# Board_connectors.net
KiCad netlist of a schematic drawn in Altium Designer
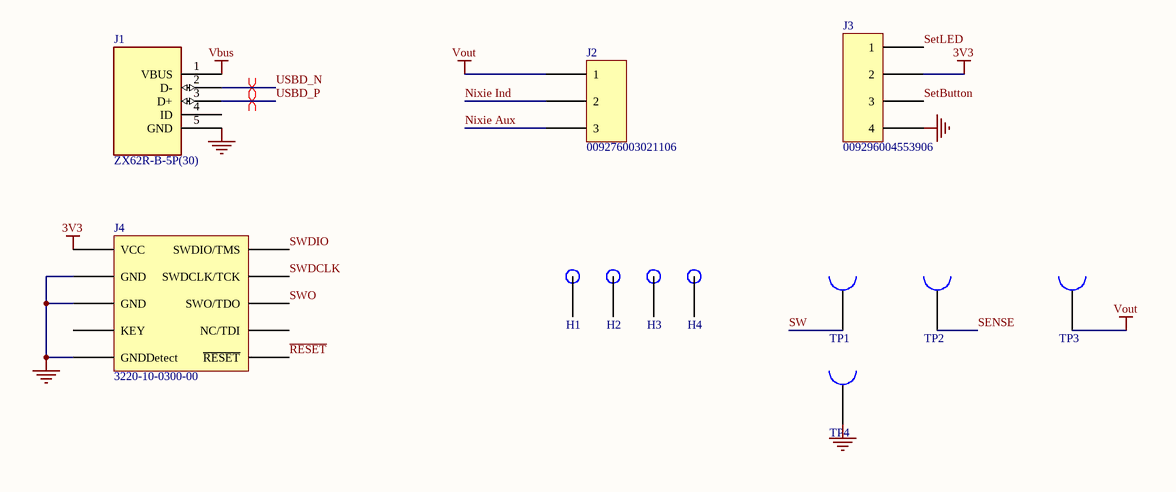
[diagram p0: Board connectors.SchDoc]

(export (version "E")
  (design (tool "Eeschema 10.0.6"))
  (components
    (comp (ref "H1")
      (value "M3 PLATED TIGHT FIT PAN HEAD")
      (footprint "M3 PLATED TIGHT PAN HEAD")
      (description "M3 x 0.5mm plated tight fit pan head")
      (libsource (lib "Connectors") (part "M3 PLATED TIGHT FIT PAN HEAD"))
    )
    (comp (ref "H2")
      (value "M3 PLATED TIGHT FIT PAN HEAD")
      (footprint "M3 PLATED TIGHT PAN HEAD")
      (description "M3 x 0.5mm plated tight fit pan head")
      (libsource (lib "Connectors") (part "M3 PLATED TIGHT FIT PAN HEAD"))
    )
    (comp (ref "H3")
      (value "M3 PLATED TIGHT FIT PAN HEAD")
      (footprint "M3 PLATED TIGHT PAN HEAD")
      (description "M3 x 0.5mm plated tight fit pan head")
      (libsource (lib "Connectors") (part "M3 PLATED TIGHT FIT PAN HEAD"))
    )
    (comp (ref "H4")
      (value "M3 PLATED TIGHT FIT PAN HEAD")
      (footprint "M3 PLATED TIGHT PAN HEAD")
      (description "M3 x 0.5mm plated tight fit pan head")
      (libsource (lib "Connectors") (part "M3 PLATED TIGHT FIT PAN HEAD"))
    )
    (comp (ref "J1")
      (value "ZX62R-B-5P(30)")
      (footprint "HRS_ZX62R-B-5P(30)_ZX62R-B-5P(30)(Primary)")
      (fields (field (name "MANUFACTURER") "Hirose"))
      (libsource (lib "Connectors") (part "ZX62R-B-5P(30)"))
    )
    (comp (ref "J2")
      (value "009276003021106")
      (footprint "009276003021106")
      (description "CONN TERM BLOCK 3 POS WTB")
      (fields (field (name "MANUFACTURER") "Kyocera") (field (name "VOLTAGE") "250V"))
      (libsource (lib "Connectors") (part "009276003021106"))
    )
    (comp (ref "J3")
      (value "009296004553906")
      (footprint "009296004553906")
      (description "Headers & Wire Housings 4WAY POKE HOME VERTICAL TOP MOUNT")
      (fields (field (name "MANUFACTURER") "Kyocera AVX"))
      (libsource (lib "Connectors") (part "009296004553906"))
    )
    (comp (ref "J4")
      (value "3220-10-0300-00")
      (footprint "3220-10-0300-00")
      (description "IDC BOX HEADER 0.050 10 POS")
      (fields (field (name "MANUFACTURER") "CNC Tech"))
      (libsource (lib "Connectors") (part "3220-10-0300-00"))
    )
    (comp (ref "TP1")
      (value "SMD test point")
      (footprint "2mm SMD test point")
      (libsource (lib "Connectors") (part "SMD test point"))
    )
    (comp (ref "TP2")
      (value "SMD test point")
      (footprint "2mm SMD test point")
      (libsource (lib "Connectors") (part "SMD test point"))
    )
    (comp (ref "TP3")
      (value "SMD test point")
      (footprint "2mm SMD test point")
      (libsource (lib "Connectors") (part "SMD test point"))
    )
    (comp (ref "TP4")
      (value "SMD test point")
      (footprint "2mm SMD test point")
      (libsource (lib "Connectors") (part "SMD test point"))
    )
  )
  (nets
    (net (code "1") (name "/Nixie Aux") (class "Default")
      (node (ref "J2") (pin "3") (pinfunction "3_3") (pintype "passive"))
    )
    (net (code "2") (name "/Nixie Ind") (class "Default")
      (node (ref "J2") (pin "2") (pinfunction "2_2") (pintype "passive"))
    )
    (net (code "3") (name "/SENSE") (class "Default")
      (node (ref "TP2") (pin "1") (pinfunction "1_1") (pintype "passive"))
    )
    (net (code "4") (name "/SW") (class "Default")
      (node (ref "TP1") (pin "1") (pinfunction "1_1") (pintype "passive"))
    )
    (net (code "5") (name "/SWDCLK") (class "Default")
      (node (ref "J4") (pin "4") (pinfunction "SWDCLK/TCK_4") (pintype "passive"))
    )
    (net (code "6") (name "/SWDIO") (class "Default")
      (node (ref "J4") (pin "2") (pinfunction "SWDIO/TMS_2") (pintype "passive"))
    )
    (net (code "7") (name "/SWO") (class "Default")
      (node (ref "J4") (pin "6") (pinfunction "SWO/TDO_6") (pintype "passive"))
    )
    (net (code "8") (name "/SetButton") (class "Default")
      (node (ref "J3") (pin "3") (pinfunction "3_3") (pintype "passive"))
    )
    (net (code "9") (name "/SetLED") (class "Default")
      (node (ref "J3") (pin "1") (pinfunction "1_1") (pintype "passive"))
    )
    (net (code "10") (name "/USBD_N") (class "Default")
      (node (ref "J1") (pin "2") (pinfunction "D-_2") (pintype "bidirectional"))
    )
    (net (code "11") (name "/USBD_P") (class "Default")
      (node (ref "J1") (pin "3") (pinfunction "D+_3") (pintype "bidirectional"))
    )
    (net (code "12") (name "/~{RESET}") (class "Default")
      (node (ref "J4") (pin "10") (pinfunction "~{RESET}_10") (pintype "passive"))
    )
    (net (code "13") (name "3V3") (class "Default")
      (node (ref "J3") (pin "2") (pinfunction "2_2") (pintype "passive"))
      (node (ref "J4") (pin "1") (pinfunction "VCC_1") (pintype "passive"))
    )
    (net (code "14") (name "GND") (class "Default")
      (node (ref "J1") (pin "5") (pinfunction "GND_5") (pintype "power_in"))
      (node (ref "J3") (pin "4") (pinfunction "4_4") (pintype "passive"))
      (node (ref "J4") (pin "3") (pinfunction "GND_3") (pintype "passive"))
      (node (ref "J4") (pin "5") (pinfunction "GND_5") (pintype "passive"))
      (node (ref "J4") (pin "9") (pinfunction "GNDDetect_9") (pintype "passive"))
      (node (ref "TP4") (pin "1") (pinfunction "1_1") (pintype "passive"))
    )
    (net (code "15") (name "Vbus") (class "Default")
      (node (ref "J1") (pin "1") (pinfunction "VBUS_1") (pintype "power_in"))
    )
    (net (code "16") (name "Vout") (class "Default")
      (node (ref "J2") (pin "1") (pinfunction "1_1") (pintype "passive"))
      (node (ref "TP3") (pin "1") (pinfunction "1_1") (pintype "passive"))
    )
    (net (code "17") (name "unconnected-(H1-Pad1)") (class "Default")
      (node (ref "H1") (pin "1") (pinfunction "1_1") (pintype "passive"))
    )
    (net (code "18") (name "unconnected-(H2-Pad1)") (class "Default")
      (node (ref "H2") (pin "1") (pinfunction "1_1") (pintype "passive"))
    )
    (net (code "19") (name "unconnected-(H3-Pad1)") (class "Default")
      (node (ref "H3") (pin "1") (pinfunction "1_1") (pintype "passive"))
    )
    (net (code "20") (name "unconnected-(H4-Pad1)") (class "Default")
      (node (ref "H4") (pin "1") (pinfunction "1_1") (pintype "passive"))
    )
    (net (code "21") (name "unconnected-(J1-ID-Pad4)") (class "Default")
      (node (ref "J1") (pin "4") (pinfunction "ID_4") (pintype "passive"))
    )
    (net (code "22") (name "unconnected-(J4-KEY-Pad7)") (class "Default")
      (node (ref "J4") (pin "7") (pinfunction "KEY_7") (pintype "passive"))
    )
    (net (code "23") (name "unconnected-(J4-NC{slash}TDI-Pad8)") (class "Default")
      (node (ref "J4") (pin "8") (pinfunction "NC/TDI_8") (pintype "passive"))
    )
  )
)
